# assignment.net
KiCad netlist of a schematic drawn in EAGLE
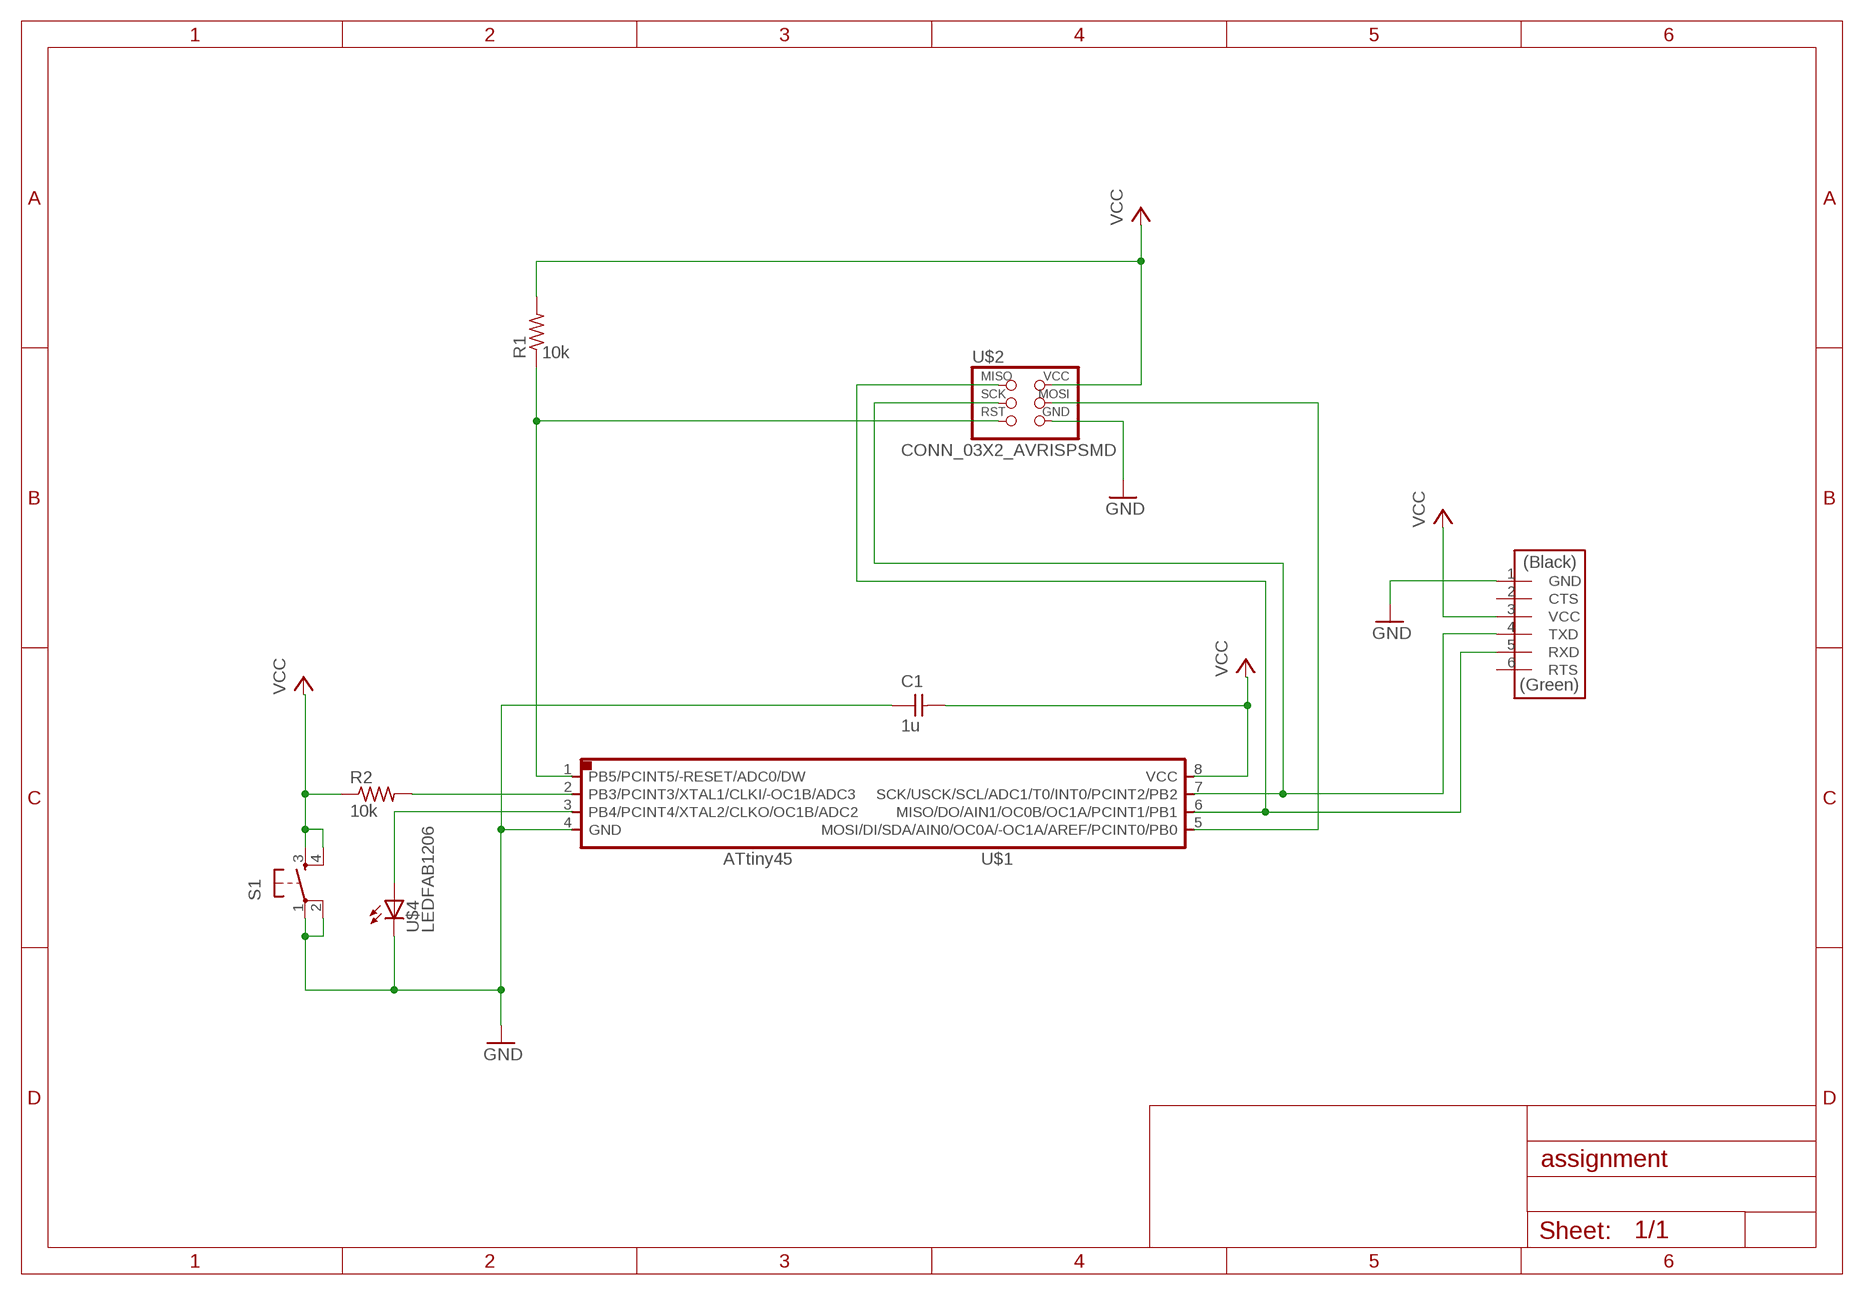
[diagram p0: schematic, sheet 1]

(export (version "E")
  (design (tool "Eeschema 10.0.6"))
  (components
    (comp (ref "C1")
      (value "1u")
      (footprint "eagle-import:C1206FAB")
      (libsource (lib "eagle-import") (part "CAP_UNPOLARIZEDFAB"))
    )
    (comp (ref "R1")
      (value "10k")
      (footprint "eagle-import:R1206FAB")
      (libsource (lib "eagle-import") (part "R1206FAB"))
    )
    (comp (ref "R2")
      (value "10k")
      (footprint "eagle-import:R1206FAB")
      (libsource (lib "eagle-import") (part "R1206FAB"))
    )
    (comp (ref "S1")
      (value "SW_SWITCH_TACTILE_6MM6MM_SWITCH")
      (footprint "eagle-import:6MM_SWITCH")
      (libsource (lib "eagle-import") (part "SW_SWITCH_TACTILE_6MM6MM_SWITCH"))
    )
    (comp (ref "U$1")
      (value "UC_ATTINY45SI")
      (footprint "eagle-import:SOIC8")
      (libsource (lib "eagle-import") (part "UC_ATTINY45SI"))
    )
    (comp (ref "U$2")
      (value "CONN_03X2_AVRISPSMD")
      (footprint "eagle-import:2X03SMD")
      (libsource (lib "eagle-import") (part "CONN_03X2_AVRISPSMD"))
    )
    (comp (ref "U$3")
      (value "CONN_06_FTDI-SMD-HEADER")
      (footprint "eagle-import:1X06SMD")
      (libsource (lib "eagle-import") (part "CONN_06_FTDI-SMD-HEADER"))
    )
    (comp (ref "U$4")
      (value "LEDFAB1206")
      (footprint "eagle-import:LED1206FAB")
      (libsource (lib "eagle-import") (part "LEDFAB1206"))
    )
  )
  (nets
    (net (code "1") (name "GND") (class "Default")
      (node (ref "C1") (pin "1") (pinfunction "1_1") (pintype "passive"))
      (node (ref "S1") (pin "1") (pinfunction "P_1") (pintype "passive"))
      (node (ref "S1") (pin "2") (pinfunction "P1_2") (pintype "passive"))
      (node (ref "U$1") (pin "4") (pinfunction "GND_4") (pintype "bidirectional"))
      (node (ref "U$2") (pin "6") (pinfunction "GND_6") (pintype "passive"))
      (node (ref "U$3") (pin "1") (pinfunction "GND_1") (pintype "bidirectional"))
      (node (ref "U$4") (pin "2") (pinfunction "C_2") (pintype "passive"))
    )
    (net (code "2") (name "Net-(U$1-MISO{slash}DO{slash}AIN1{slash}OC0B{slash}OC1A{slash}PCINT1{slash}PB1)") (class "Default")
      (node (ref "U$1") (pin "6") (pinfunction "MISO/DO/AIN1/OC0B/OC1A/PCINT1/PB1_6") (pintype "bidirectional"))
      (node (ref "U$2") (pin "1") (pinfunction "MISO_1") (pintype "passive"))
      (node (ref "U$3") (pin "5") (pinfunction "RXD_5") (pintype "bidirectional"))
    )
    (net (code "3") (name "Net-(U$1-MOSI{slash}DI{slash}SDA{slash}AIN0{slash}OC0A{slash}-OC1A{slash}AREF{slash}PCINT0{slash}PB0)") (class "Default")
      (node (ref "U$1") (pin "5") (pinfunction "MOSI/DI/SDA/AIN0/OC0A/-OC1A/AREF/PCINT0/PB0_5") (pintype "bidirectional"))
      (node (ref "U$2") (pin "4") (pinfunction "MOSI_4") (pintype "passive"))
    )
    (net (code "4") (name "Net-(U$1-PB3{slash}PCINT3{slash}XTAL1{slash}CLKI{slash}-OC1B{slash}ADC3)") (class "Default")
      (node (ref "R2") (pin "2") (pinfunction "2_2") (pintype "passive"))
      (node (ref "U$1") (pin "2") (pinfunction "PB3/PCINT3/XTAL1/CLKI/-OC1B/ADC3_2") (pintype "bidirectional"))
    )
    (net (code "5") (name "Net-(U$1-PB4{slash}PCINT4{slash}XTAL2{slash}CLKO{slash}OC1B{slash}ADC2)") (class "Default")
      (node (ref "U$1") (pin "3") (pinfunction "PB4/PCINT4/XTAL2/CLKO/OC1B/ADC2_3") (pintype "bidirectional"))
      (node (ref "U$4") (pin "1") (pinfunction "A_1") (pintype "passive"))
    )
    (net (code "6") (name "Net-(U$1-PB5{slash}PCINT5{slash}-RESET{slash}ADC0{slash}DW)") (class "Default")
      (node (ref "R1") (pin "1") (pinfunction "1_1") (pintype "passive"))
      (node (ref "U$1") (pin "1") (pinfunction "PB5/PCINT5/-RESET/ADC0/DW_1") (pintype "bidirectional"))
      (node (ref "U$2") (pin "5") (pinfunction "RST_5") (pintype "passive"))
    )
    (net (code "7") (name "Net-(U$1-SCK{slash}USCK{slash}SCL{slash}ADC1{slash}T0{slash}INT0{slash}PCINT2{slash}PB2)") (class "Default")
      (node (ref "U$1") (pin "7") (pinfunction "SCK/USCK/SCL/ADC1/T0/INT0/PCINT2/PB2_7") (pintype "bidirectional"))
      (node (ref "U$2") (pin "3") (pinfunction "SCK_3") (pintype "passive"))
      (node (ref "U$3") (pin "4") (pinfunction "TXD_4") (pintype "bidirectional"))
    )
    (net (code "8") (name "VCC") (class "Default")
      (node (ref "C1") (pin "2") (pinfunction "2_2") (pintype "passive"))
      (node (ref "R1") (pin "2") (pinfunction "2_2") (pintype "passive"))
      (node (ref "R2") (pin "1") (pinfunction "1_1") (pintype "passive"))
      (node (ref "S1") (pin "3") (pinfunction "S_3") (pintype "passive"))
      (node (ref "S1") (pin "4") (pinfunction "S1_4") (pintype "passive"))
      (node (ref "U$1") (pin "8") (pinfunction "VCC_8") (pintype "bidirectional"))
      (node (ref "U$2") (pin "2") (pinfunction "VCC_2") (pintype "passive"))
      (node (ref "U$3") (pin "3") (pinfunction "VCC_3") (pintype "bidirectional"))
    )
    (net (code "9") (name "unconnected-(U$3-CTS-Pad2)") (class "Default")
      (node (ref "U$3") (pin "2") (pinfunction "CTS_2") (pintype "bidirectional"))
    )
    (net (code "10") (name "unconnected-(U$3-RTS-Pad6)") (class "Default")
      (node (ref "U$3") (pin "6") (pinfunction "RTS_6") (pintype "bidirectional"))
    )
  )
)
